# Chiqoo3.net
KiCad netlist of a schematic drawn in EAGLE
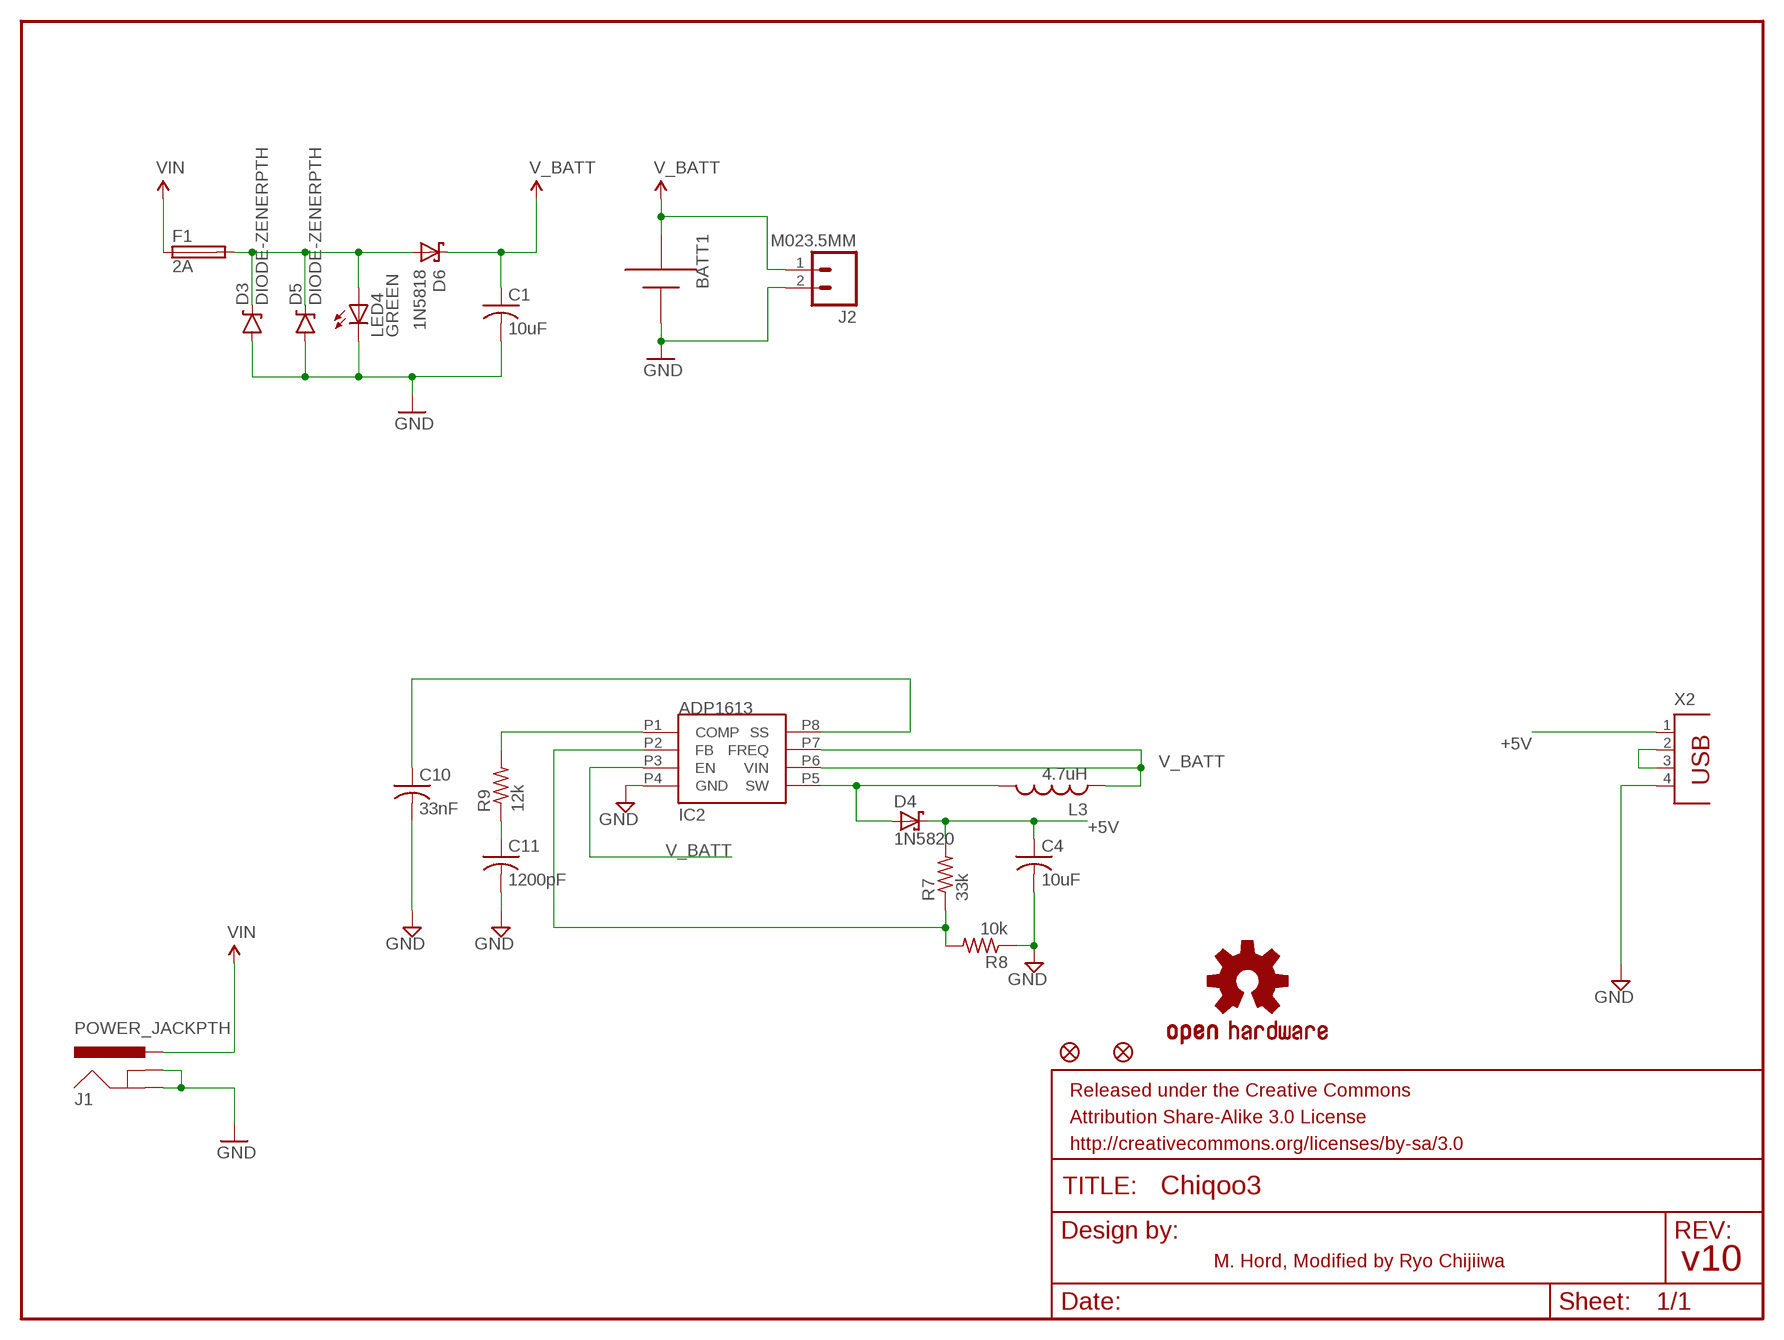
[diagram p0: schematic, sheet 1]

(export (version "E")
  (design (tool "Eeschema 10.0.6"))
  (components
    (comp (ref "BATT1")
      (value "18650-HOLDER")
      (footprint "eagle-import:BK-18650-PC2")
      (libsource (lib "eagle-import") (part "18650-HOLDER"))
    )
    (comp (ref "C1")
      (value "10uF")
      (footprint "eagle-import:C050-024X044")
      (libsource (lib "eagle-import") (part "C-US050-024X044"))
    )
    (comp (ref "C4")
      (value "10uF")
      (footprint "eagle-import:C050-024X044")
      (libsource (lib "eagle-import") (part "C-US050-024X044"))
    )
    (comp (ref "C10")
      (value "33nF")
      (footprint "eagle-import:C050-024X044")
      (libsource (lib "eagle-import") (part "resistor_C-US050-024X044"))
    )
    (comp (ref "C11")
      (value "1200pF")
      (footprint "eagle-import:C025-025X050")
      (libsource (lib "eagle-import") (part "resistor_C-US025-025X050"))
    )
    (comp (ref "D3")
      (value "DIODE-ZENERPTH")
      (footprint "eagle-import:DIODE-ZENER")
      (libsource (lib "eagle-import") (part "DIODE-ZENERPTH"))
    )
    (comp (ref "D4")
      (value "1N5820")
      (footprint "eagle-import:DIODE")
      (libsource (lib "eagle-import") (part "SCHOTTKY-DIODE"))
    )
    (comp (ref "D5")
      (value "DIODE-ZENERPTH")
      (footprint "eagle-import:DIODE-ZENER")
      (libsource (lib "eagle-import") (part "DIODE-ZENERPTH"))
    )
    (comp (ref "D6")
      (value "1N5818")
      (footprint "eagle-import:DIODE-5")
      (libsource (lib "eagle-import") (part "SCHOTTKY-DIODEDIODE-5"))
    )
    (comp (ref "F1")
      (value "2A")
      (footprint "eagle-import:TE5")
      (libsource (lib "eagle-import") (part "TE5"))
    )
    (comp (ref "FID1")
      (value "FIDUCIAL1X2")
      (footprint "eagle-import:FIDUCIAL-1X2")
      (libsource (lib "eagle-import") (part "FIDUCIAL1X2"))
    )
    (comp (ref "FID2")
      (value "FIDUCIAL1X2")
      (footprint "eagle-import:FIDUCIAL-1X2")
      (libsource (lib "eagle-import") (part "FIDUCIAL1X2"))
    )
    (comp (ref "FRAME1")
      (value "FRAME-LETTER")
      (footprint "eagle-import:CREATIVE_COMMONS")
      (libsource (lib "eagle-import") (part "FRAME-LETTER"))
    )
    (comp (ref "IC2")
      (value "ADP1613")
      (footprint "eagle-import:RM-8")
      (libsource (lib "eagle-import") (part "ADP1613"))
    )
    (comp (ref "J1")
      (value "POWER_JACKPTH")
      (footprint "eagle-import:POWER_JACK_PTH")
      (libsource (lib "eagle-import") (part "POWER_JACKPTH"))
    )
    (comp (ref "J2")
      (value "M023.5MM")
      (footprint "eagle-import:SCREWTERMINAL-3.5MM-2")
      (libsource (lib "eagle-import") (part "M023.5MM"))
    )
    (comp (ref "L3")
      (value "4.7uH")
      (footprint "eagle-import:L-5MM-THRUHOLE")
      (libsource (lib "eagle-import") (part "L-5MM-THRUHOLE"))
    )
    (comp (ref "LED4")
      (value "GREEN")
      (footprint "eagle-import:LED3MM")
      (libsource (lib "eagle-import") (part "LED3MM"))
    )
    (comp (ref "LOGO2")
      (value "OSHW-LOGOM")
      (footprint "eagle-import:OSHW-LOGO-M")
      (libsource (lib "eagle-import") (part "OSHW-LOGOM"))
    )
    (comp (ref "R7")
      (value "33k")
      (footprint "eagle-import:0204_5")
      (libsource (lib "eagle-import") (part "R-US_0204/5"))
    )
    (comp (ref "R8")
      (value "10k")
      (footprint "eagle-import:0204_5")
      (libsource (lib "eagle-import") (part "R-US_0204/5"))
    )
    (comp (ref "R9")
      (value "12k")
      (footprint "eagle-import:0204_5")
      (libsource (lib "eagle-import") (part "R-US_0204/5"))
    )
    (comp (ref "X2")
      (value "PN87520")
      (footprint "eagle-import:PN87520")
      (libsource (lib "eagle-import") (part "PN87520"))
    )
  )
  (nets
    (net (code "1") (name "/+5V") (class "Default")
      (node (ref "C4") (pin "1") (pinfunction "1_1") (pintype "passive"))
      (node (ref "D4") (pin "CATHODE") (pinfunction "C_CATHODE") (pintype "passive"))
      (node (ref "R7") (pin "2") (pinfunction "2_2") (pintype "passive"))
      (node (ref "X2") (pin "1") (pinfunction "1_1") (pintype "passive"))
    )
    (net (code "2") (name "GND") (class "Default")
      (node (ref "BATT1") (pin "-") (pinfunction "--_-") (pintype "bidirectional"))
      (node (ref "C1") (pin "2") (pinfunction "2_2") (pintype "passive"))
      (node (ref "C10") (pin "2") (pinfunction "2_2") (pintype "passive"))
      (node (ref "C11") (pin "2") (pinfunction "2_2") (pintype "passive"))
      (node (ref "C4") (pin "2") (pinfunction "2_2") (pintype "passive"))
      (node (ref "D3") (pin "P$2") (pinfunction "A_P$2") (pintype "passive"))
      (node (ref "D5") (pin "P$2") (pinfunction "A_P$2") (pintype "passive"))
      (node (ref "IC2") (pin "P4") (pinfunction "GND_P4") (pintype "bidirectional"))
      (node (ref "J1") (pin "GND") (pinfunction "GND_GND") (pintype "bidirectional"))
      (node (ref "J1") (pin "GNDBREAK") (pinfunction "GNDBREAK_GNDBREAK") (pintype "bidirectional"))
      (node (ref "J2") (pin "2") (pinfunction "2_2") (pintype "passive"))
      (node (ref "LED4") (pin "K") (pinfunction "C_K") (pintype "passive"))
      (node (ref "R8") (pin "1") (pinfunction "1_1") (pintype "passive"))
      (node (ref "X2") (pin "4") (pinfunction "4_4") (pintype "passive"))
    )
    (net (code "3") (name "Net-(C11-Pad1)") (class "Default")
      (node (ref "C11") (pin "1") (pinfunction "1_1") (pintype "passive"))
      (node (ref "R9") (pin "1") (pinfunction "1_1") (pintype "passive"))
    )
    (net (code "4") (name "Net-(D3-C)") (class "Default")
      (node (ref "D3") (pin "P$1") (pinfunction "C_P$1") (pintype "passive"))
      (node (ref "D5") (pin "P$1") (pinfunction "C_P$1") (pintype "passive"))
      (node (ref "D6") (pin "A") (pinfunction "A_A") (pintype "passive"))
      (node (ref "F1") (pin "2") (pinfunction "2_2") (pintype "passive"))
      (node (ref "LED4") (pin "A") (pinfunction "A_A") (pintype "passive"))
    )
    (net (code "5") (name "Net-(D4-A)") (class "Default")
      (node (ref "D4") (pin "ANNODE") (pinfunction "A_ANNODE") (pintype "passive"))
      (node (ref "IC2") (pin "P5") (pinfunction "SW_P5") (pintype "bidirectional"))
      (node (ref "L3") (pin "2") (pinfunction "2_2") (pintype "passive"))
    )
    (net (code "6") (name "Net-(IC2-COMP)") (class "Default")
      (node (ref "IC2") (pin "P1") (pinfunction "COMP_P1") (pintype "bidirectional"))
      (node (ref "R9") (pin "2") (pinfunction "2_2") (pintype "passive"))
    )
    (net (code "7") (name "Net-(IC2-FB)") (class "Default")
      (node (ref "IC2") (pin "P2") (pinfunction "FB_P2") (pintype "bidirectional"))
      (node (ref "R7") (pin "1") (pinfunction "1_1") (pintype "passive"))
      (node (ref "R8") (pin "2") (pinfunction "2_2") (pintype "passive"))
    )
    (net (code "8") (name "Net-(IC2-SS)") (class "Default")
      (node (ref "C10") (pin "1") (pinfunction "1_1") (pintype "passive"))
      (node (ref "IC2") (pin "P8") (pinfunction "SS_P8") (pintype "bidirectional"))
    )
    (net (code "9") (name "Net-(X2-Pad2)") (class "Default")
      (node (ref "X2") (pin "2") (pinfunction "2_2") (pintype "passive"))
      (node (ref "X2") (pin "3") (pinfunction "3_3") (pintype "passive"))
    )
    (net (code "10") (name "VIN") (class "Default")
      (node (ref "F1") (pin "1") (pinfunction "1_1") (pintype "passive"))
      (node (ref "J1") (pin "PWR") (pinfunction "PWR_PWR") (pintype "bidirectional"))
    )
    (net (code "11") (name "V_BATT") (class "Default")
      (node (ref "BATT1") (pin "+") (pinfunction "++_+") (pintype "bidirectional"))
      (node (ref "C1") (pin "1") (pinfunction "1_1") (pintype "passive"))
      (node (ref "D6") (pin "C") (pinfunction "C_C") (pintype "passive"))
      (node (ref "IC2") (pin "P3") (pinfunction "EN_P3") (pintype "bidirectional"))
      (node (ref "IC2") (pin "P6") (pinfunction "VIN_P6") (pintype "bidirectional"))
      (node (ref "IC2") (pin "P7") (pinfunction "FREQ_P7") (pintype "bidirectional"))
      (node (ref "J2") (pin "1") (pinfunction "1_1") (pintype "passive"))
      (node (ref "L3") (pin "1") (pinfunction "1_1") (pintype "passive"))
    )
  )
)
